# p10_control.net
KiCad netlist of a schematic drawn in EAGLE
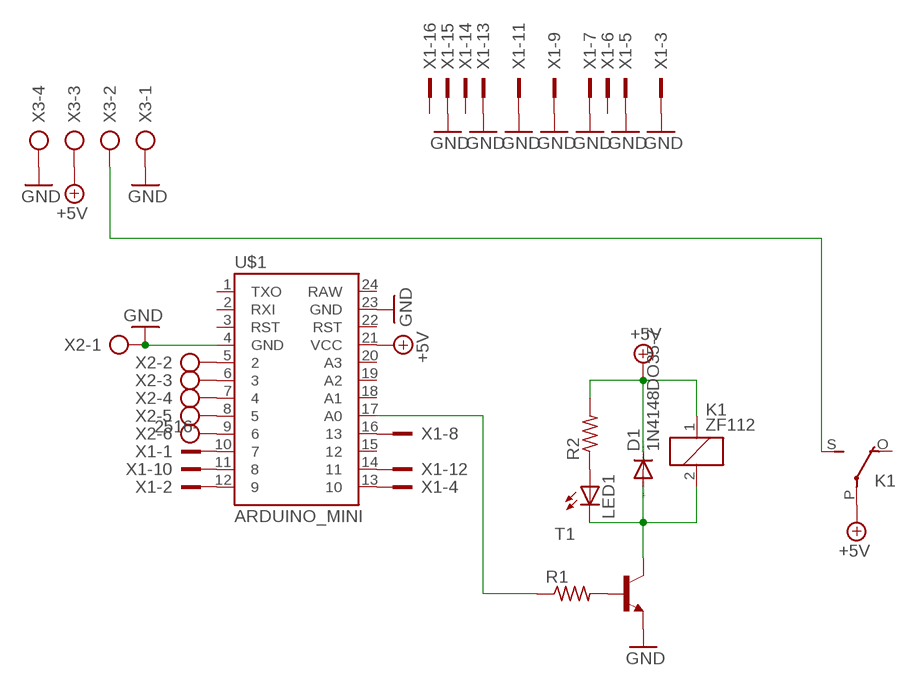
[diagram p0: schematic, sheet 1]

(export (version "E")
  (design (tool "Eeschema 10.0.6"))
  (components
    (comp (ref "D1")
      (value "1N4148DO35-7")
      (footprint "eagle-import:DO35-7")
      (libsource (lib "eagle-import") (part "1N4148DO35-7"))
    )
    (comp (ref "K1")
      (value "ZF112")
      (footprint "eagle-import:ZF112")
      (libsource (lib "eagle-import") (part "ZF112"))
    )
    (comp (ref "LED1")
      (value "LED3MM")
      (footprint "eagle-import:LED3MM")
      (libsource (lib "eagle-import") (part "LED3MM"))
    )
    (comp (ref "R1")
      (value "R-US_0207/7")
      (footprint "eagle-import:0207_7")
      (libsource (lib "eagle-import") (part "R-US_0207/7"))
    )
    (comp (ref "R2")
      (value "R-US_0207/10")
      (footprint "eagle-import:0207_10")
      (libsource (lib "eagle-import") (part "R-US_0207/10"))
    )
    (comp (ref "T1")
      (value "2N3904-NPN-TO92-EBC")
      (footprint "eagle-import:TO92-EBC")
      (libsource (lib "eagle-import") (part "-NPN-TO92-EBC2N3904"))
    )
    (comp (ref "U$1")
      (value "ARDUINO_MINI")
      (footprint "eagle-import:ARDUINO_MINI")
      (libsource (lib "eagle-import") (part "ARDUINO_MINI"))
    )
    (comp (ref "X1")
      (value "2516-")
      (footprint "eagle-import:PAK100_2500-16")
      (libsource (lib "eagle-import") (part "2516-"))
    )
    (comp (ref "X2")
      (value "AK500/6")
      (footprint "eagle-import:AK500_6")
      (libsource (lib "eagle-import") (part "AK500/6"))
    )
    (comp (ref "X3")
      (value "AK500/4")
      (footprint "eagle-import:AK500_4")
      (libsource (lib "eagle-import") (part "AK500/4"))
    )
  )
  (nets
    (net (code "1") (name "+5V") (class "Default")
      (node (ref "D1") (pin "C") (pinfunction "C_C") (pintype "passive"))
      (node (ref "K1") (pin "1") (pinfunction "1_1") (pintype "passive"))
      (node (ref "K1") (pin "P") (pinfunction "P_P") (pintype "passive"))
      (node (ref "R2") (pin "2") (pinfunction "2_2") (pintype "passive"))
      (node (ref "U$1") (pin "21") (pinfunction "VCC_21") (pintype "bidirectional"))
      (node (ref "X3") (pin "3") (pinfunction "KL_3") (pintype "passive"))
    )
    (net (code "2") (name "GND") (class "Default")
      (node (ref "T1") (pin "E") (pinfunction "E_E") (pintype "passive"))
      (node (ref "U$1") (pin "23") (pinfunction "GND_23") (pintype "bidirectional"))
      (node (ref "U$1") (pin "4") (pinfunction "GND_4") (pintype "bidirectional"))
      (node (ref "X1") (pin "11") (pinfunction "KL_11") (pintype "passive"))
      (node (ref "X1") (pin "13") (pinfunction "KL_13") (pintype "passive"))
      (node (ref "X1") (pin "15") (pinfunction "KL_15") (pintype "passive"))
      (node (ref "X1") (pin "3") (pinfunction "KL_3") (pintype "passive"))
      (node (ref "X1") (pin "5") (pinfunction "KL_5") (pintype "passive"))
      (node (ref "X1") (pin "7") (pinfunction "KL_7") (pintype "passive"))
      (node (ref "X1") (pin "9") (pinfunction "KL_9") (pintype "passive"))
      (node (ref "X2") (pin "1") (pinfunction "KL_1") (pintype "passive"))
      (node (ref "X3") (pin "1") (pinfunction "KL_1") (pintype "passive"))
      (node (ref "X3") (pin "4") (pinfunction "KL_4") (pintype "passive"))
    )
    (net (code "3") (name "Net-(LED1-C)") (class "Default")
      (node (ref "D1") (pin "A") (pinfunction "A_A") (pintype "passive"))
      (node (ref "K1") (pin "2") (pinfunction "2_2") (pintype "passive"))
      (node (ref "LED1") (pin "K") (pinfunction "C_K") (pintype "passive"))
      (node (ref "T1") (pin "C") (pinfunction "C_C") (pintype "passive"))
    )
    (net (code "4") (name "Net-(LED1-PadA)") (class "Default")
      (node (ref "LED1") (pin "A") (pinfunction "A_A") (pintype "passive"))
      (node (ref "R2") (pin "1") (pinfunction "1_1") (pintype "passive"))
    )
    (net (code "5") (name "Net-(R1-Pad2)") (class "Default")
      (node (ref "R1") (pin "2") (pinfunction "2_2") (pintype "passive"))
      (node (ref "T1") (pin "B") (pinfunction "B_B") (pintype "passive"))
    )
    (net (code "6") (name "Net-(U$1-2)") (class "Default")
      (node (ref "U$1") (pin "5") (pinfunction "2_5") (pintype "bidirectional"))
      (node (ref "X2") (pin "2") (pinfunction "KL_2") (pintype "passive"))
    )
    (net (code "7") (name "Net-(U$1-3)") (class "Default")
      (node (ref "U$1") (pin "6") (pinfunction "3_6") (pintype "bidirectional"))
      (node (ref "X2") (pin "3") (pinfunction "KL_3") (pintype "passive"))
    )
    (net (code "8") (name "Net-(U$1-4)") (class "Default")
      (node (ref "U$1") (pin "7") (pinfunction "4_7") (pintype "bidirectional"))
      (node (ref "X2") (pin "4") (pinfunction "KL_4") (pintype "passive"))
    )
    (net (code "9") (name "Net-(U$1-5)") (class "Default")
      (node (ref "U$1") (pin "8") (pinfunction "5_8") (pintype "bidirectional"))
      (node (ref "X2") (pin "5") (pinfunction "KL_5") (pintype "passive"))
    )
    (net (code "10") (name "Net-(U$1-6)") (class "Default")
      (node (ref "U$1") (pin "9") (pinfunction "6_9") (pintype "bidirectional"))
      (node (ref "X2") (pin "6") (pinfunction "KL_6") (pintype "passive"))
    )
    (net (code "11") (name "Net-(U$1-7)") (class "Default")
      (node (ref "U$1") (pin "10") (pinfunction "7_10") (pintype "bidirectional"))
      (node (ref "X1") (pin "1") (pinfunction "KL_1") (pintype "passive"))
    )
    (net (code "12") (name "Net-(U$1-8)") (class "Default")
      (node (ref "U$1") (pin "11") (pinfunction "8_11") (pintype "bidirectional"))
      (node (ref "X1") (pin "10") (pinfunction "KL_10") (pintype "passive"))
    )
    (net (code "13") (name "Net-(U$1-9)") (class "Default")
      (node (ref "U$1") (pin "12") (pinfunction "9_12") (pintype "bidirectional"))
      (node (ref "X1") (pin "2") (pinfunction "KL_2") (pintype "passive"))
    )
    (net (code "14") (name "Net-(U$1-10)") (class "Default")
      (node (ref "U$1") (pin "13") (pinfunction "10_13") (pintype "bidirectional"))
      (node (ref "X1") (pin "4") (pinfunction "KL_4") (pintype "passive"))
    )
    (net (code "15") (name "Net-(U$1-11)") (class "Default")
      (node (ref "U$1") (pin "14") (pinfunction "11_14") (pintype "bidirectional"))
      (node (ref "X1") (pin "12") (pinfunction "KL_12") (pintype "passive"))
    )
    (net (code "16") (name "Net-(U$1-13)") (class "Default")
      (node (ref "U$1") (pin "16") (pinfunction "13_16") (pintype "bidirectional"))
      (node (ref "X1") (pin "8") (pinfunction "KL_8") (pintype "passive"))
    )
    (net (code "17") (name "Net-(U$1-A0)") (class "Default")
      (node (ref "R1") (pin "1") (pinfunction "1_1") (pintype "passive"))
      (node (ref "U$1") (pin "17") (pinfunction "A0_17") (pintype "bidirectional"))
    )
    (net (code "18") (name "Net-(X3B-KL)") (class "Default")
      (node (ref "K1") (pin "S") (pinfunction "S_S") (pintype "passive"))
      (node (ref "X3") (pin "2") (pinfunction "KL_2") (pintype "passive"))
    )
    (net (code "19") (name "unconnected-(K1-PadO)") (class "Default")
      (node (ref "K1") (pin "O") (pinfunction "O_O") (pintype "passive"))
    )
    (net (code "20") (name "unconnected-(U$1-12-Pad15)") (class "Default")
      (node (ref "U$1") (pin "15") (pinfunction "12_15") (pintype "bidirectional"))
    )
    (net (code "21") (name "unconnected-(U$1-A1-Pad18)") (class "Default")
      (node (ref "U$1") (pin "18") (pinfunction "A1_18") (pintype "bidirectional"))
    )
    (net (code "22") (name "unconnected-(U$1-A2-Pad19)") (class "Default")
      (node (ref "U$1") (pin "19") (pinfunction "A2_19") (pintype "bidirectional"))
    )
    (net (code "23") (name "unconnected-(U$1-A3-Pad20)") (class "Default")
      (node (ref "U$1") (pin "20") (pinfunction "A3_20") (pintype "bidirectional"))
    )
    (net (code "24") (name "unconnected-(U$1-RAW-Pad24)") (class "Default")
      (node (ref "U$1") (pin "24") (pinfunction "RAW_24") (pintype "bidirectional"))
    )
    (net (code "25") (name "unconnected-(U$1-RST-Pad3)") (class "Default")
      (node (ref "U$1") (pin "3") (pinfunction "RST_3") (pintype "bidirectional"))
    )
    (net (code "26") (name "unconnected-(U$1-RST-Pad22)") (class "Default")
      (node (ref "U$1") (pin "22") (pinfunction "RST_22") (pintype "bidirectional"))
    )
    (net (code "27") (name "unconnected-(U$1-RXI-Pad2)") (class "Default")
      (node (ref "U$1") (pin "2") (pinfunction "RXI_2") (pintype "bidirectional"))
    )
    (net (code "28") (name "unconnected-(U$1-TXO-Pad1)") (class "Default")
      (node (ref "U$1") (pin "1") (pinfunction "TXO_1") (pintype "bidirectional"))
    )
    (net (code "29") (name "unconnected-(X1F-KL-Pad14)") (class "Default")
      (node (ref "X1") (pin "14") (pinfunction "KL_14") (pintype "passive"))
    )
    (net (code "30") (name "unconnected-(X1H-KL-Pad16)") (class "Default")
      (node (ref "X1") (pin "16") (pinfunction "KL_16") (pintype "passive"))
    )
    (net (code "31") (name "unconnected-(X1M-KL-Pad6)") (class "Default")
      (node (ref "X1") (pin "6") (pinfunction "KL_6") (pintype "passive"))
    )
  )
)
